# motor_28.net
KiCad netlist of a schematic drawn in Altium Designer
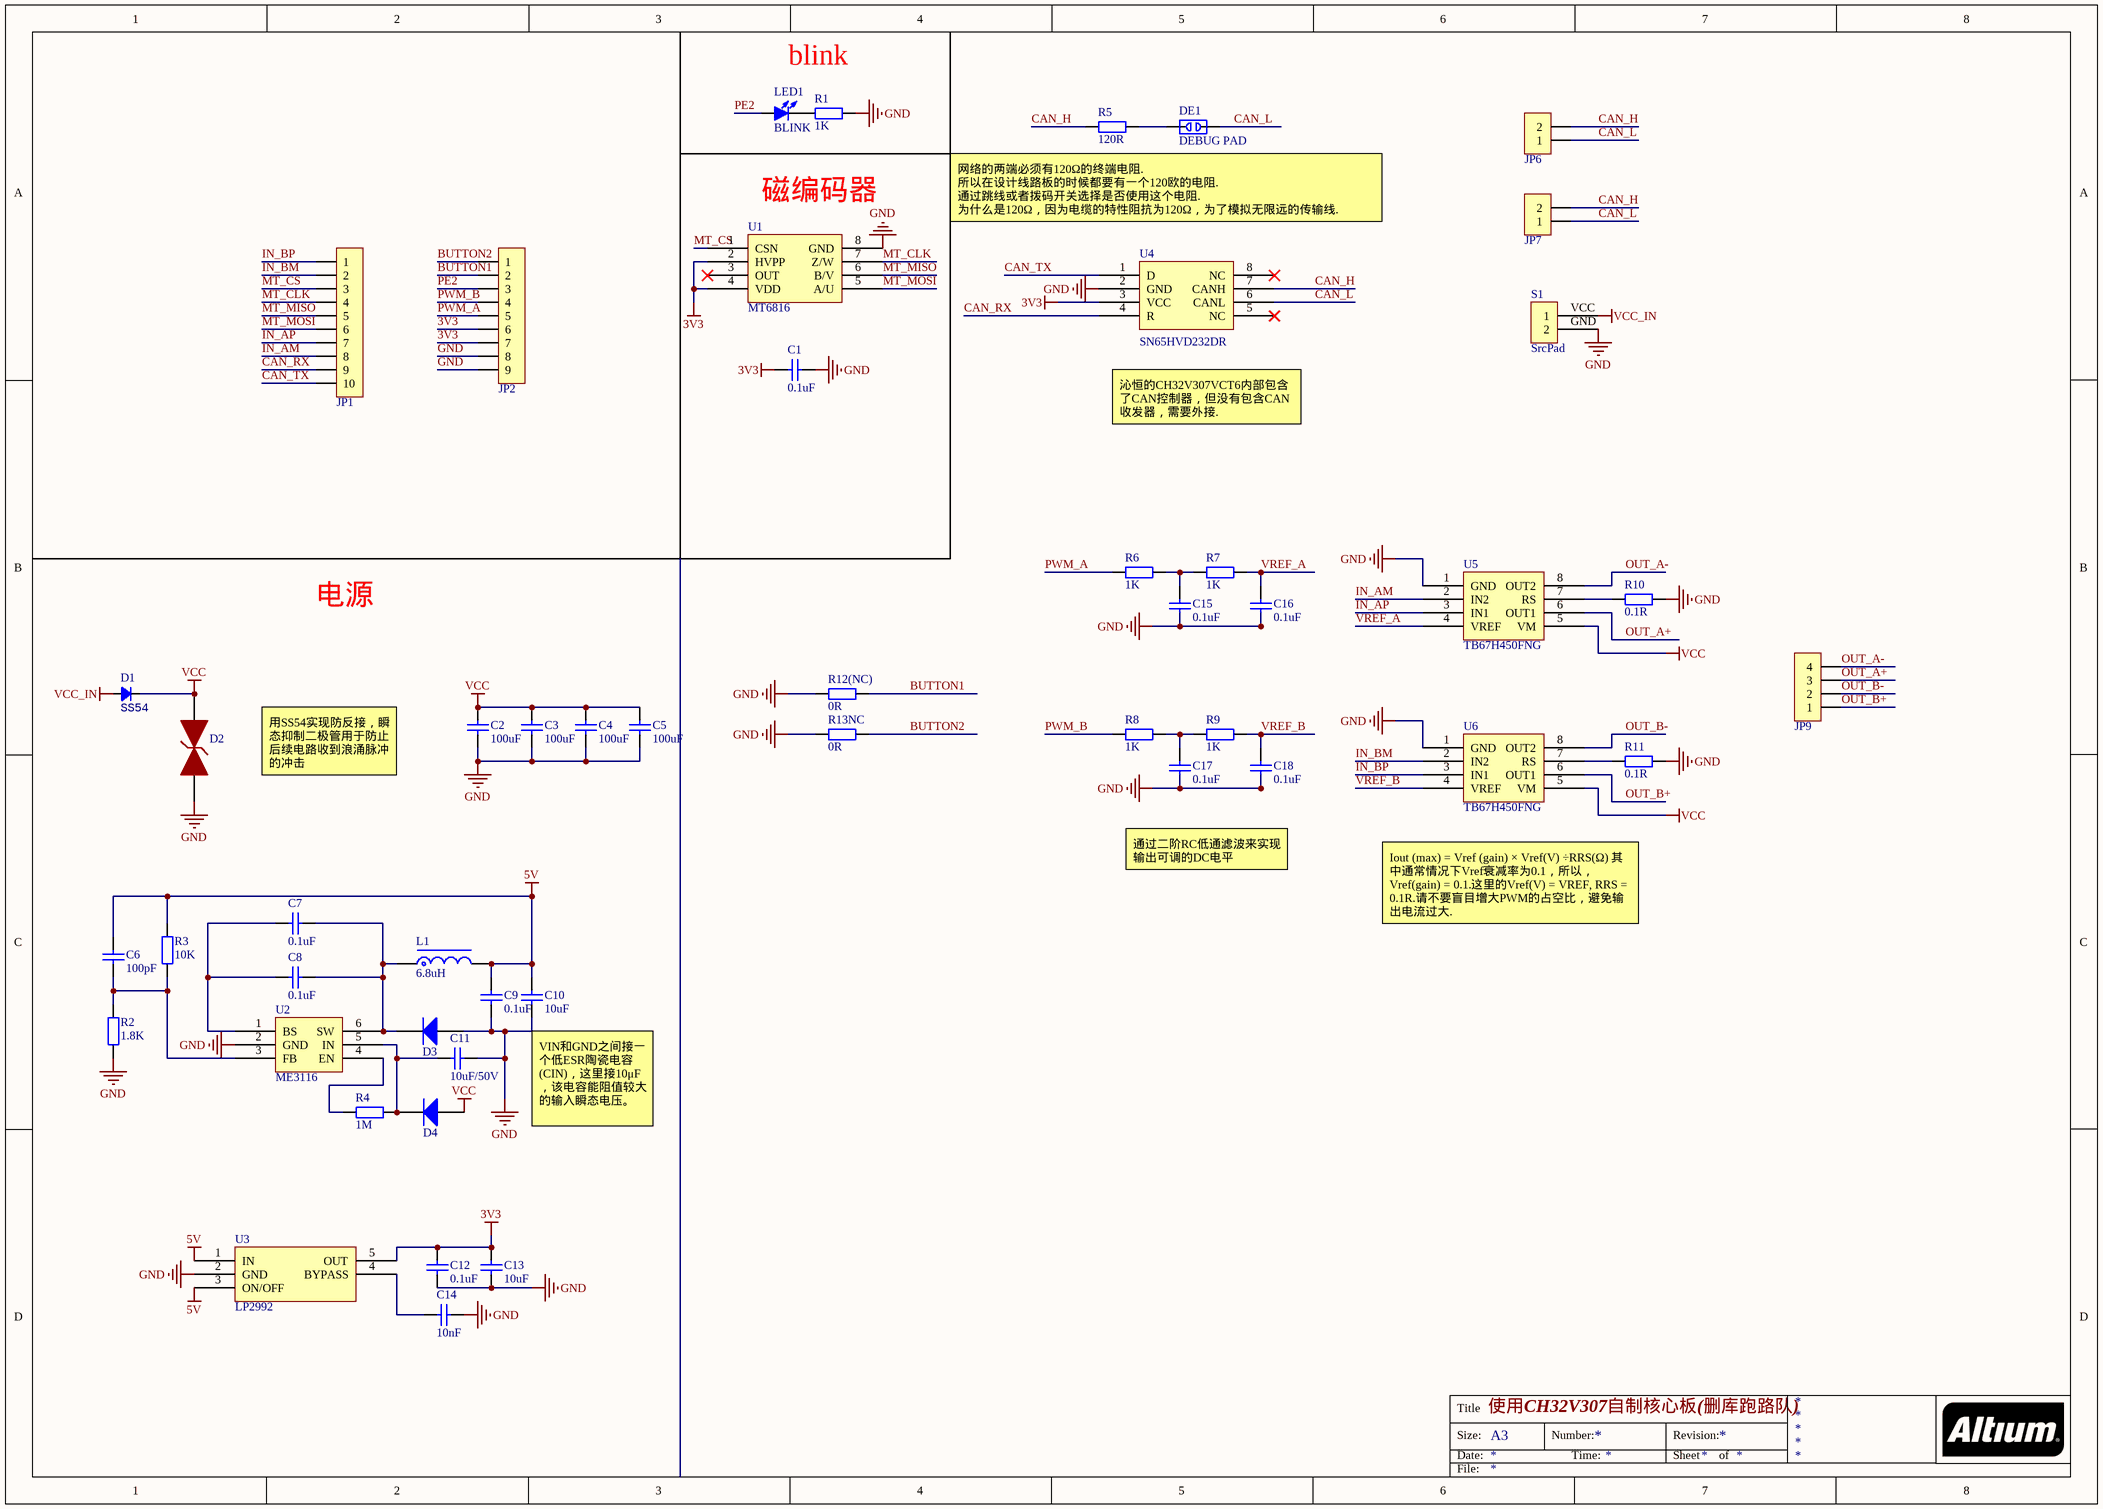
[diagram p0: motor_28.SchDoc]

(export (version "E")
  (design (tool "Eeschema 10.0.6"))
  (components
    (comp (ref "C1")
      (value "0.1uF")
      (footprint "C0805_L")
      (description "贴片电容/MLCC电容")
      (libsource (lib "0.1 - 电阻-电容-电感-晶振-晶体-磁珠-电位器-法拉电容-馈通电容") (part "C"))
    )
    (comp (ref "C2")
      (value "100uF")
      (footprint "C1206_L")
      (description "贴片电容/MLCC电容")
      (libsource (lib "0.1 - 电阻-电容-电感-晶振-晶体-磁珠-电位器-法拉电容-馈通电容") (part "C"))
    )
    (comp (ref "C3")
      (value "100uF")
      (footprint "C1206_L")
      (description "贴片电容/MLCC电容")
      (libsource (lib "0.1 - 电阻-电容-电感-晶振-晶体-磁珠-电位器-法拉电容-馈通电容") (part "C"))
    )
    (comp (ref "C4")
      (value "100uF")
      (footprint "C1206_L")
      (description "贴片电容/MLCC电容")
      (libsource (lib "0.1 - 电阻-电容-电感-晶振-晶体-磁珠-电位器-法拉电容-馈通电容") (part "C"))
    )
    (comp (ref "C5")
      (value "100uF")
      (footprint "C1206_L")
      (description "贴片电容/MLCC电容")
      (libsource (lib "0.1 - 电阻-电容-电感-晶振-晶体-磁珠-电位器-法拉电容-馈通电容") (part "C"))
    )
    (comp (ref "C6")
      (value "100pF")
      (footprint "C0402_L")
      (description "贴片电容/MLCC电容")
      (libsource (lib "0.1 - 电阻-电容-电感-晶振-晶体-磁珠-电位器-法拉电容-馈通电容") (part "C"))
    )
    (comp (ref "C7")
      (value "0.1uF")
      (footprint "C0402_L")
      (description "贴片电容/MLCC电容")
      (libsource (lib "0.1 - 电阻-电容-电感-晶振-晶体-磁珠-电位器-法拉电容-馈通电容") (part "C"))
    )
    (comp (ref "C8")
      (value "0.1uF")
      (footprint "C0402_L")
      (description "贴片电容/MLCC电容")
      (libsource (lib "0.1 - 电阻-电容-电感-晶振-晶体-磁珠-电位器-法拉电容-馈通电容") (part "C"))
    )
    (comp (ref "C9")
      (value "0.1uF")
      (footprint "C0402_L")
      (description "贴片电容/MLCC电容")
      (libsource (lib "0.1 - 电阻-电容-电感-晶振-晶体-磁珠-电位器-法拉电容-馈通电容") (part "C"))
    )
    (comp (ref "C10")
      (value "10uF")
      (footprint "C0402_L")
      (description "贴片电容/MLCC电容")
      (libsource (lib "0.1 - 电阻-电容-电感-晶振-晶体-磁珠-电位器-法拉电容-馈通电容") (part "C"))
    )
    (comp (ref "C11")
      (value "10uF/50V")
      (footprint "C0603_L")
      (description "陶瓷电容")
      (libsource (lib "0.1 - 电阻-电容-电感-晶振-晶体-磁珠-电位器-法拉电容-馈通电容") (part "C"))
    )
    (comp (ref "C12")
      (value "0.1uF")
      (footprint "C0402_L")
      (description "贴片电容/MLCC电容")
      (libsource (lib "0.1 - 电阻-电容-电感-晶振-晶体-磁珠-电位器-法拉电容-馈通电容") (part "C"))
    )
    (comp (ref "C13")
      (value "10uF")
      (footprint "C0402_L")
      (description "贴片电容/MLCC电容")
      (libsource (lib "0.1 - 电阻-电容-电感-晶振-晶体-磁珠-电位器-法拉电容-馈通电容") (part "C"))
    )
    (comp (ref "C14")
      (value "10nF")
      (footprint "C0402_L")
      (description "贴片电容/MLCC电容")
      (libsource (lib "0.1 - 电阻-电容-电感-晶振-晶体-磁珠-电位器-法拉电容-馈通电容") (part "C"))
    )
    (comp (ref "C15")
      (value "0.1uF")
      (footprint "C0402_L")
      (description "贴片电容/MLCC电容")
      (libsource (lib "0.1 - 电阻-电容-电感-晶振-晶体-磁珠-电位器-法拉电容-馈通电容") (part "C"))
    )
    (comp (ref "C16")
      (value "0.1uF")
      (footprint "C0402_L")
      (description "贴片电容/MLCC电容")
      (libsource (lib "0.1 - 电阻-电容-电感-晶振-晶体-磁珠-电位器-法拉电容-馈通电容") (part "C"))
    )
    (comp (ref "C17")
      (value "0.1uF")
      (footprint "C0402_L")
      (description "贴片电容/MLCC电容")
      (libsource (lib "0.1 - 电阻-电容-电感-晶振-晶体-磁珠-电位器-法拉电容-馈通电容") (part "C"))
    )
    (comp (ref "C18")
      (value "0.1uF")
      (footprint "C0402_L")
      (description "贴片电容/MLCC电容")
      (libsource (lib "0.1 - 电阻-电容-电感-晶振-晶体-磁珠-电位器-法拉电容-馈通电容") (part "C"))
    )
    (comp (ref "D1")
      (value "SS54")
      (footprint "SMA")
      (description "Diode")
      (libsource (lib "KitSprout") (part "Diode_SMA"))
    )
    (comp (ref "D2") (value "SMBJ28CA") (footprint "SMB") (libsource (lib "MyPcbLib") (part "SMBJ28CA")))
    (comp (ref "D3")
      (value "二极管-5819W")
      (footprint "SOD-323")
      (description "40V")
      (libsource (lib "0.2 - 二极管-TVS-ESD-整流桥-放电管") (part "二极管-5819W"))
    )
    (comp (ref "D4")
      (value "二极管-5819W")
      (footprint "SOD-323")
      (description "40V")
      (libsource (lib "0.2 - 二极管-TVS-ESD-整流桥-放电管") (part "二极管-5819W"))
    )
    (comp (ref "DE1")
      (value "DEBUG PAD")
      (footprint "DEBUG_A")
      (description "调试断点焊盘")
      (libsource (lib "0.5 - 按键_开关_蜂鸣器_保险丝_电池_测试点_Mark点_铜柱") (part "DEBUG"))
    )
    (comp (ref "JP1")
      (value "CON-10P")
      (footprint "FPC1.0-WT-10P")
      (description "10P连接器")
      (libsource (lib "5.0 - 1.00mm连接器(FPC1.0_SH1.0_1.0排针排母)") (part "Header 10"))
    )
    (comp (ref "JP2")
      (value "CON-9P")
      (footprint "FPC1.0-WT-9P")
      (description "9P连接器")
      (libsource (lib "5.0 - 1.00mm连接器(FPC1.0_SH1.0_1.0排针排母)") (part "Header 9"))
    )
    (comp (ref "JP6")
      (value "CON-2P")
      (footprint "FPC1.0-WT-2P")
      (description "2P连接器")
      (libsource (lib "5.0 - 1.00mm连接器(FPC1.0_SH1.0_1.0排针排母)") (part "Header 2"))
    )
    (comp (ref "JP7")
      (value "CON-2P")
      (footprint "FPC1.0-WT-2P")
      (description "2P连接器")
      (libsource (lib "5.0 - 1.00mm连接器(FPC1.0_SH1.0_1.0排针排母)") (part "Header 2"))
    )
    (comp (ref "JP9")
      (value "HDR-1X4")
      (footprint "XH2.54-LI-4P")
      (description "4P接插件")
      (libsource (lib "5.5 - 2.54mm连接器(KF2EDGK_XH2.54_2.54排针排母)") (part "Header 4"))
    )
    (comp (ref "L1")
      (value "6.8uH")
      (footprint "L-SMD-0420")
      (description "一体成型电感")
      (libsource (lib "0.1 - 电阻-电容-电感-晶振-晶体-磁珠-电位器-法拉电容-馈通电容") (part "L-Molding Choke"))
    )
    (comp (ref "LED1")
      (value "BLINK")
      (footprint "LED0805_G")
      (description "贴片LED")
      (libsource (lib "0.3 - LED发光二极管-IR二极管_接收管-光耦") (part "LED-SMD"))
    )
    (comp (ref "R1")
      (value "1K")
      (footprint "R0402_L")
      (description "贴片电阻")
      (libsource (lib "0.1 - 电阻-电容-电感-晶振-晶体-磁珠-电位器-法拉电容-馈通电容") (part "R"))
    )
    (comp (ref "R2")
      (value "1.8K")
      (footprint "R0402_L")
      (description "贴片电阻")
      (libsource (lib "0.1 - 电阻-电容-电感-晶振-晶体-磁珠-电位器-法拉电容-馈通电容") (part "R"))
    )
    (comp (ref "R3")
      (value "10K")
      (footprint "R0402_L")
      (description "贴片电阻")
      (libsource (lib "0.1 - 电阻-电容-电感-晶振-晶体-磁珠-电位器-法拉电容-馈通电容") (part "R"))
    )
    (comp (ref "R4")
      (value "1M")
      (footprint "R0402_L")
      (description "贴片电阻")
      (libsource (lib "0.1 - 电阻-电容-电感-晶振-晶体-磁珠-电位器-法拉电容-馈通电容") (part "R"))
    )
    (comp (ref "R5")
      (value "120R")
      (footprint "R0402_L")
      (description "贴片电阻")
      (libsource (lib "0.1 - 电阻-电容-电感-晶振-晶体-磁珠-电位器-法拉电容-馈通电容") (part "R"))
    )
    (comp (ref "R6")
      (value "1K")
      (footprint "R0402_L")
      (description "贴片电阻")
      (libsource (lib "0.1 - 电阻-电容-电感-晶振-晶体-磁珠-电位器-法拉电容-馈通电容") (part "R"))
    )
    (comp (ref "R7")
      (value "1K")
      (footprint "R0402_L")
      (description "贴片电阻")
      (libsource (lib "0.1 - 电阻-电容-电感-晶振-晶体-磁珠-电位器-法拉电容-馈通电容") (part "R"))
    )
    (comp (ref "R8")
      (value "1K")
      (footprint "R0402_L")
      (description "贴片电阻")
      (libsource (lib "0.1 - 电阻-电容-电感-晶振-晶体-磁珠-电位器-法拉电容-馈通电容") (part "R"))
    )
    (comp (ref "R9")
      (value "1K")
      (footprint "R0402_L")
      (description "贴片电阻")
      (libsource (lib "0.1 - 电阻-电容-电感-晶振-晶体-磁珠-电位器-法拉电容-馈通电容") (part "R"))
    )
    (comp (ref "R10")
      (value "0.1R")
      (footprint "R1206_L")
      (description "贴片电阻")
      (libsource (lib "0.1 - 电阻-电容-电感-晶振-晶体-磁珠-电位器-法拉电容-馈通电容") (part "R"))
    )
    (comp (ref "R11")
      (value "0.1R")
      (footprint "R1206_L")
      (description "贴片电阻")
      (libsource (lib "0.1 - 电阻-电容-电感-晶振-晶体-磁珠-电位器-法拉电容-馈通电容") (part "R"))
    )
    (comp (ref "R12(NC)")
      (value "0R")
      (footprint "R0603_L")
      (description "贴片电阻")
      (libsource (lib "0.1 - 电阻-电容-电感-晶振-晶体-磁珠-电位器-法拉电容-馈通电容") (part "R"))
    )
    (comp (ref "R13NC")
      (value "0R")
      (footprint "R0603_L")
      (description "贴片电阻")
      (libsource (lib "0.1 - 电阻-电容-电感-晶振-晶体-磁珠-电位器-法拉电容-馈通电容") (part "R"))
    )
    (comp (ref "S1") (value "SrcPad") (footprint "SrcPad") (libsource (lib "Motor28") (part "SrcPad")))
    (comp (ref "U1") (value "MT6816") (footprint "SOP8_L") (libsource (lib "MT6816") (part "MT6816")))
    (comp (ref "U2") (value "ME3116") (footprint "SOT23-6") (libsource (lib "MT6816") (part "ME3116")))
    (comp (ref "U3") (value "LP2992") (footprint "SOT23-5") (libsource (lib "MT6816") (part "LP2992")))
    (comp (ref "U4")
      (value "SN65HVD232D")
      (footprint "SOIC-8")
      (fields
        (field (name "MANUFACTURER") "Texas Instruments")
        (field (name "MANUFACTURER PART NUMBER") "SN65HVD232DR")
      )
      (libsource (lib "0.8 - 常见芯片") (part "SN65HVD232D"))
    )
    (comp (ref "U5")
      (value "TB67H450FNG")
      (footprint "HSOP-8:HSOP-8")
      (libsource (lib "MT6816") (part "TB67H450FNG"))
    )
    (comp (ref "U6")
      (value "TB67H450FNG")
      (footprint "HSOP-8:HSOP-8")
      (libsource (lib "MT6816") (part "TB67H450FNG"))
    )
  )
  (nets
    (net (code "1") (name "/BUTTON1") (class "Default")
      (node (ref "JP2") (pin "2") (pinfunction "2_2") (pintype "passive"))
      (node (ref "R12(NC)") (pin "2") (pinfunction "2_2") (pintype "passive"))
    )
    (net (code "2") (name "/BUTTON2") (class "Default")
      (node (ref "JP2") (pin "1") (pinfunction "1_1") (pintype "passive"))
      (node (ref "R13NC") (pin "2") (pinfunction "2_2") (pintype "passive"))
    )
    (net (code "3") (name "/CAN_H") (class "Default")
      (node (ref "JP6") (pin "2") (pinfunction "2_2") (pintype "passive"))
      (node (ref "JP7") (pin "2") (pinfunction "2_2") (pintype "passive"))
      (node (ref "R5") (pin "1") (pinfunction "1_1") (pintype "passive"))
      (node (ref "U4") (pin "7") (pinfunction "CANH_7") (pintype "passive"))
    )
    (net (code "4") (name "/CAN_L") (class "Default")
      (node (ref "DE1") (pin "2") (pinfunction "2_2") (pintype "passive"))
      (node (ref "JP6") (pin "1") (pinfunction "1_1") (pintype "passive"))
      (node (ref "JP7") (pin "1") (pinfunction "1_1") (pintype "passive"))
      (node (ref "U4") (pin "6") (pinfunction "CANL_6") (pintype "passive"))
    )
    (net (code "5") (name "/CAN_RX") (class "Default")
      (node (ref "JP1") (pin "9") (pinfunction "9_9") (pintype "passive"))
      (node (ref "U4") (pin "4") (pinfunction "R_4") (pintype "passive"))
    )
    (net (code "6") (name "/CAN_TX") (class "Default")
      (node (ref "JP1") (pin "10") (pinfunction "10_10") (pintype "passive"))
      (node (ref "U4") (pin "1") (pinfunction "D_1") (pintype "passive"))
    )
    (net (code "7") (name "/IN_AM") (class "Default")
      (node (ref "JP1") (pin "8") (pinfunction "8_8") (pintype "passive"))
      (node (ref "U5") (pin "2") (pinfunction "IN2_2") (pintype "passive"))
    )
    (net (code "8") (name "/IN_AP") (class "Default")
      (node (ref "JP1") (pin "7") (pinfunction "7_7") (pintype "passive"))
      (node (ref "U5") (pin "3") (pinfunction "IN1_3") (pintype "passive"))
    )
    (net (code "9") (name "/IN_BM") (class "Default")
      (node (ref "JP1") (pin "2") (pinfunction "2_2") (pintype "passive"))
      (node (ref "U6") (pin "2") (pinfunction "IN2_2") (pintype "passive"))
    )
    (net (code "10") (name "/IN_BP") (class "Default")
      (node (ref "JP1") (pin "1") (pinfunction "1_1") (pintype "passive"))
      (node (ref "U6") (pin "3") (pinfunction "IN1_3") (pintype "passive"))
    )
    (net (code "11") (name "/MT_CLK") (class "Default")
      (node (ref "JP1") (pin "4") (pinfunction "4_4") (pintype "passive"))
      (node (ref "U1") (pin "7") (pinfunction "Z/W_7") (pintype "passive"))
    )
    (net (code "12") (name "/MT_CS") (class "Default")
      (node (ref "JP1") (pin "3") (pinfunction "3_3") (pintype "passive"))
      (node (ref "U1") (pin "1") (pinfunction "CSN_1") (pintype "passive"))
    )
    (net (code "13") (name "/MT_MISO") (class "Default")
      (node (ref "JP1") (pin "5") (pinfunction "5_5") (pintype "passive"))
      (node (ref "U1") (pin "6") (pinfunction "B/V_6") (pintype "passive"))
    )
    (net (code "14") (name "/MT_MOSI") (class "Default")
      (node (ref "JP1") (pin "6") (pinfunction "6_6") (pintype "passive"))
      (node (ref "U1") (pin "5") (pinfunction "A/U_5") (pintype "passive"))
    )
    (net (code "15") (name "/OUT_A+") (class "Default")
      (node (ref "JP9") (pin "3") (pinfunction "3_3") (pintype "passive"))
      (node (ref "U5") (pin "6") (pinfunction "OUT1_6") (pintype "passive"))
    )
    (net (code "16") (name "/OUT_A-") (class "Default")
      (node (ref "JP9") (pin "4") (pinfunction "4_4") (pintype "passive"))
      (node (ref "U5") (pin "8") (pinfunction "OUT2_8") (pintype "passive"))
    )
    (net (code "17") (name "/OUT_B+") (class "Default")
      (node (ref "JP9") (pin "1") (pinfunction "1_1") (pintype "passive"))
      (node (ref "U6") (pin "6") (pinfunction "OUT1_6") (pintype "passive"))
    )
    (net (code "18") (name "/OUT_B-") (class "Default")
      (node (ref "JP9") (pin "2") (pinfunction "2_2") (pintype "passive"))
      (node (ref "U6") (pin "8") (pinfunction "OUT2_8") (pintype "passive"))
    )
    (net (code "19") (name "/PE2") (class "Default")
      (node (ref "JP2") (pin "3") (pinfunction "3_3") (pintype "passive"))
      (node (ref "LED1") (pin "1") (pinfunction "A_1") (pintype "passive"))
    )
    (net (code "20") (name "/PWM_A") (class "Default")
      (node (ref "JP2") (pin "5") (pinfunction "5_5") (pintype "passive"))
      (node (ref "R6") (pin "1") (pinfunction "1_1") (pintype "passive"))
    )
    (net (code "21") (name "/PWM_B") (class "Default")
      (node (ref "JP2") (pin "4") (pinfunction "4_4") (pintype "passive"))
      (node (ref "R8") (pin "1") (pinfunction "1_1") (pintype "passive"))
    )
    (net (code "22") (name "/VREF_A") (class "Default")
      (node (ref "C16") (pin "2") (pinfunction "2_2") (pintype "passive"))
      (node (ref "R7") (pin "2") (pinfunction "2_2") (pintype "passive"))
      (node (ref "U5") (pin "4") (pinfunction "VREF_4") (pintype "passive"))
    )
    (net (code "23") (name "/VREF_B") (class "Default")
      (node (ref "C18") (pin "2") (pinfunction "2_2") (pintype "passive"))
      (node (ref "R9") (pin "2") (pinfunction "2_2") (pintype "passive"))
      (node (ref "U6") (pin "4") (pinfunction "VREF_4") (pintype "passive"))
    )
    (net (code "24") (name "3V3") (class "Default")
      (node (ref "C1") (pin "1") (pinfunction "1_1") (pintype "passive"))
      (node (ref "C12") (pin "2") (pinfunction "2_2") (pintype "passive"))
      (node (ref "C13") (pin "2") (pinfunction "2_2") (pintype "passive"))
      (node (ref "JP2") (pin "6") (pinfunction "6_6") (pintype "passive"))
      (node (ref "JP2") (pin "7") (pinfunction "7_7") (pintype "passive"))
      (node (ref "U1") (pin "2") (pinfunction "HVPP_2") (pintype "passive"))
      (node (ref "U1") (pin "4") (pinfunction "VDD_4") (pintype "passive"))
      (node (ref "U3") (pin "5") (pinfunction "OUT_5") (pintype "passive"))
      (node (ref "U4") (pin "3") (pinfunction "VCC_3") (pintype "passive"))
    )
    (net (code "25") (name "5V") (class "Default")
      (node (ref "C10") (pin "2") (pinfunction "2_2") (pintype "passive"))
      (node (ref "C6") (pin "2") (pinfunction "2_2") (pintype "passive"))
      (node (ref "C9") (pin "1") (pinfunction "1_1") (pintype "passive"))
      (node (ref "L1") (pin "2") (pinfunction "2_2") (pintype "passive"))
      (node (ref "R3") (pin "2") (pinfunction "2_2") (pintype "passive"))
      (node (ref "U3") (pin "1") (pinfunction "IN_1") (pintype "passive"))
      (node (ref "U3") (pin "3") (pinfunction "ON/OFF_3") (pintype "passive"))
    )
    (net (code "26") (name "GND") (class "Default")
      (node (ref "C1") (pin "2") (pinfunction "2_2") (pintype "passive"))
      (node (ref "C10") (pin "1") (pinfunction "1_1") (pintype "passive"))
      (node (ref "C11") (pin "1") (pinfunction "1_1") (pintype "passive"))
      (node (ref "C12") (pin "1") (pinfunction "1_1") (pintype "passive"))
      (node (ref "C13") (pin "1") (pinfunction "1_1") (pintype "passive"))
      (node (ref "C14") (pin "1") (pinfunction "1_1") (pintype "passive"))
      (node (ref "C15") (pin "1") (pinfunction "1_1") (pintype "passive"))
      (node (ref "C16") (pin "1") (pinfunction "1_1") (pintype "passive"))
      (node (ref "C17") (pin "1") (pinfunction "1_1") (pintype "passive"))
      (node (ref "C18") (pin "1") (pinfunction "1_1") (pintype "passive"))
      (node (ref "C2") (pin "1") (pinfunction "1_1") (pintype "passive"))
      (node (ref "C3") (pin "1") (pinfunction "1_1") (pintype "passive"))
      (node (ref "C4") (pin "1") (pinfunction "1_1") (pintype "passive"))
      (node (ref "C5") (pin "1") (pinfunction "1_1") (pintype "passive"))
      (node (ref "C9") (pin "2") (pinfunction "2_2") (pintype "passive"))
      (node (ref "D2") (pin "1") (pinfunction "1_1") (pintype "passive"))
      (node (ref "D3") (pin "1") (pinfunction "A_1") (pintype "passive"))
      (node (ref "JP2") (pin "8") (pinfunction "8_8") (pintype "passive"))
      (node (ref "JP2") (pin "9") (pinfunction "9_9") (pintype "passive"))
      (node (ref "R1") (pin "2") (pinfunction "2_2") (pintype "passive"))
      (node (ref "R10") (pin "2") (pinfunction "2_2") (pintype "passive"))
      (node (ref "R11") (pin "2") (pinfunction "2_2") (pintype "passive"))
      (node (ref "R12(NC)") (pin "1") (pinfunction "1_1") (pintype "passive"))
      (node (ref "R13NC") (pin "1") (pinfunction "1_1") (pintype "passive"))
      (node (ref "R2") (pin "1") (pinfunction "1_1") (pintype "passive"))
      (node (ref "S1") (pin "GND") (pinfunction "2_GND") (pintype "passive"))
      (node (ref "U1") (pin "8") (pinfunction "GND_8") (pintype "passive"))
      (node (ref "U2") (pin "2") (pinfunction "GND_2") (pintype "passive"))
      (node (ref "U3") (pin "2") (pinfunction "GND_2") (pintype "passive"))
      (node (ref "U4") (pin "2") (pinfunction "GND_2") (pintype "passive"))
      (node (ref "U5") (pin "1") (pinfunction "GND_1") (pintype "passive"))
      (node (ref "U6") (pin "1") (pinfunction "GND_1") (pintype "passive"))
    )
    (net (code "27") (name "Net-(C15-Pad2)") (class "Default")
      (node (ref "C15") (pin "2") (pinfunction "2_2") (pintype "passive"))
      (node (ref "R6") (pin "2") (pinfunction "2_2") (pintype "passive"))
      (node (ref "R7") (pin "1") (pinfunction "1_1") (pintype "passive"))
    )
    (net (code "28") (name "Net-(C17-Pad2)") (class "Default")
      (node (ref "C17") (pin "2") (pinfunction "2_2") (pintype "passive"))
      (node (ref "R8") (pin "2") (pinfunction "2_2") (pintype "passive"))
      (node (ref "R9") (pin "1") (pinfunction "1_1") (pintype "passive"))
    )
    (net (code "29") (name "Net-(D3-K)") (class "Default")
      (node (ref "C7") (pin "1") (pinfunction "1_1") (pintype "passive"))
      (node (ref "C8") (pin "1") (pinfunction "1_1") (pintype "passive"))
      (node (ref "D3") (pin "2") (pinfunction "K_2") (pintype "passive"))
      (node (ref "L1") (pin "1") (pinfunction "1_1") (pintype "passive"))
      (node (ref "U2") (pin "6") (pinfunction "SW_6") (pintype "passive"))
    )
    (net (code "30") (name "Net-(D4-K)") (class "Default")
      (node (ref "C11") (pin "2") (pinfunction "2_2") (pintype "passive"))
      (node (ref "D4") (pin "2") (pinfunction "K_2") (pintype "passive"))
      (node (ref "R4") (pin "2") (pinfunction "2_2") (pintype "passive"))
      (node (ref "U2") (pin "5") (pinfunction "IN_5") (pintype "passive"))
    )
    (net (code "31") (name "Net-(DE1-Pad1)") (class "Default")
      (node (ref "DE1") (pin "1") (pinfunction "1_1") (pintype "passive"))
      (node (ref "R5") (pin "2") (pinfunction "2_2") (pintype "passive"))
    )
    (net (code "32") (name "Net-(LED1-K)") (class "Default")
      (node (ref "LED1") (pin "2") (pinfunction "K_2") (pintype "passive"))
      (node (ref "R1") (pin "1") (pinfunction "1_1") (pintype "passive"))
    )
    (net (code "33") (name "Net-(U2-BS)") (class "Default")
      (node (ref "C7") (pin "2") (pinfunction "2_2") (pintype "passive"))
      (node (ref "C8") (pin "2") (pinfunction "2_2") (pintype "passive"))
      (node (ref "U2") (pin "1") (pinfunction "BS_1") (pintype "passive"))
    )
    (net (code "34") (name "Net-(U2-EN)") (class "Default")
      (node (ref "R4") (pin "1") (pinfunction "1_1") (pintype "passive"))
      (node (ref "U2") (pin "4") (pinfunction "EN_4") (pintype "passive"))
    )
    (net (code "35") (name "Net-(U2-FB)") (class "Default")
      (node (ref "C6") (pin "1") (pinfunction "1_1") (pintype "passive"))
      (node (ref "R2") (pin "2") (pinfunction "2_2") (pintype "passive"))
      (node (ref "R3") (pin "1") (pinfunction "1_1") (pintype "passive"))
      (node (ref "U2") (pin "3") (pinfunction "FB_3") (pintype "passive"))
    )
    (net (code "36") (name "Net-(U3-BYPASS)") (class "Default")
      (node (ref "C14") (pin "2") (pinfunction "2_2") (pintype "passive"))
      (node (ref "U3") (pin "4") (pinfunction "BYPASS_4") (pintype "passive"))
    )
    (net (code "37") (name "Net-(U5-RS)") (class "Default")
      (node (ref "R10") (pin "1") (pinfunction "1_1") (pintype "passive"))
      (node (ref "U5") (pin "7") (pinfunction "RS_7") (pintype "passive"))
    )
    (net (code "38") (name "Net-(U6-RS)") (class "Default")
      (node (ref "R11") (pin "1") (pinfunction "1_1") (pintype "passive"))
      (node (ref "U6") (pin "7") (pinfunction "RS_7") (pintype "passive"))
    )
    (net (code "39") (name "VCC") (class "Default")
      (node (ref "C2") (pin "2") (pinfunction "2_2") (pintype "passive"))
      (node (ref "C3") (pin "2") (pinfunction "2_2") (pintype "passive"))
      (node (ref "C4") (pin "2") (pinfunction "2_2") (pintype "passive"))
      (node (ref "C5") (pin "2") (pinfunction "2_2") (pintype "passive"))
      (node (ref "D1") (pin "2") (pinfunction "K_2") (pintype "passive"))
      (node (ref "D2") (pin "2") (pinfunction "2_2") (pintype "passive"))
      (node (ref "D4") (pin "1") (pinfunction "A_1") (pintype "passive"))
      (node (ref "U5") (pin "5") (pinfunction "VM_5") (pintype "passive"))
      (node (ref "U6") (pin "5") (pinfunction "VM_5") (pintype "passive"))
    )
    (net (code "40") (name "VCC_IN") (class "Default")
      (node (ref "D1") (pin "1") (pinfunction "A_1") (pintype "passive"))
      (node (ref "S1") (pin "VCC") (pinfunction "1_VCC") (pintype "passive"))
    )
    (net (code "41") (name "unconnected-(U1-OUT-Pad3)") (class "Default")
      (node (ref "U1") (pin "3") (pinfunction "OUT_3") (pintype "passive+no_connect"))
    )
    (net (code "42") (name "unconnected-(U4-NC-Pad5)") (class "Default")
      (node (ref "U4") (pin "5") (pinfunction "NC_5") (pintype "passive+no_connect"))
    )
    (net (code "43") (name "unconnected-(U4-NC-Pad8)") (class "Default")
      (node (ref "U4") (pin "8") (pinfunction "NC_8") (pintype "passive+no_connect"))
    )
  )
)
